# MCU025B_XDS110_USB_Power.net
KiCad netlist of a schematic drawn in Altium Designer
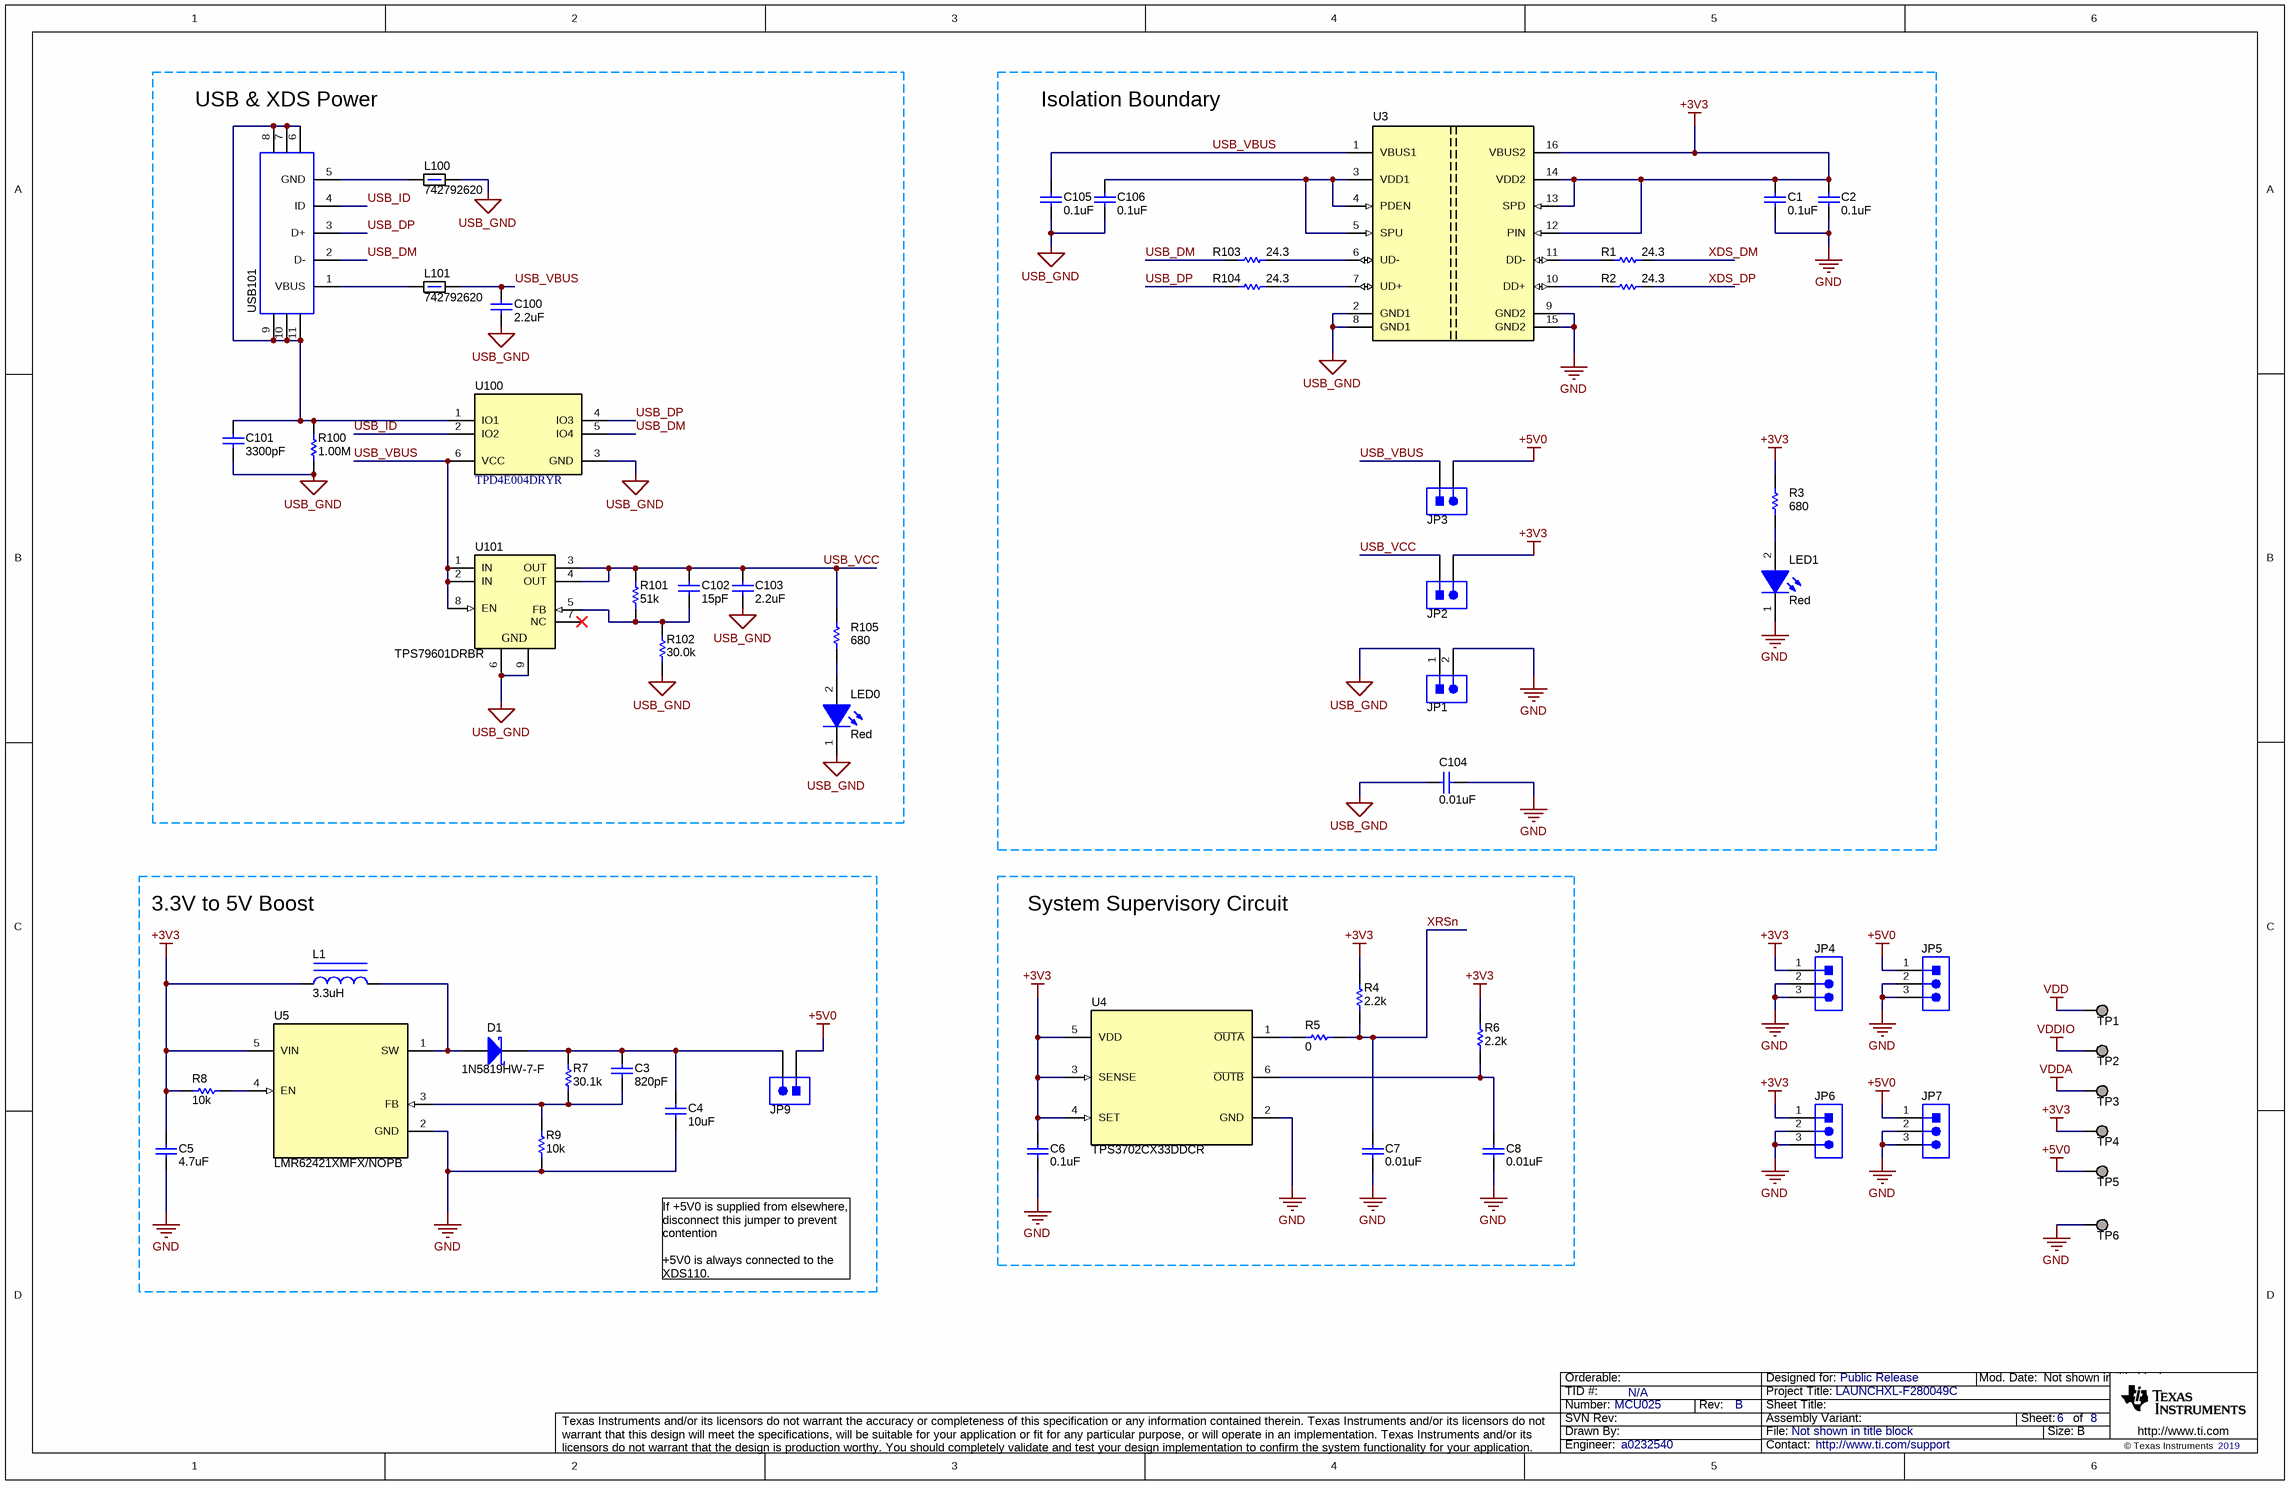
[diagram p0: MCU025B_XDS110_USB_Power.SchDoc]

(export (version "E")
  (design (tool "Eeschema 10.0.6"))
  (components
    (comp (ref "C1")
      (value "GRM155R71A104KA01D")
      (footprint "0402")
      (description "CAP, CERM, 0.1 uF, 10 V, +/- 10%, X7R, 0402")
      (fields
        (field (name "VALUEDISPLAYED") "0.1uF")
        (field (name "MANUFACTURER") "MuRata")
        (field (name "PUBLISHER") "Texas Instruments")
      )
      (libsource (lib "Altium Vault - TI") (part "Capacitor"))
    )
    (comp (ref "C2")
      (value "GRM155R71A104KA01D")
      (footprint "0402")
      (description "CAP, CERM, 0.1 uF, 10 V, +/- 10%, X7R, 0402")
      (fields
        (field (name "VALUEDISPLAYED") "0.1uF")
        (field (name "MANUFACTURER") "MuRata")
        (field (name "PUBLISHER") "Texas Instruments")
      )
      (libsource (lib "Altium Vault - TI") (part "Capacitor"))
    )
    (comp (ref "C3")
      (value "GRM1555C1H821JA01D")
      (footprint "0402")
      (description "CAP, CERM, 820 pF, 50 V, +/- 5%, C0G/NP0, 0402")
      (fields
        (field (name "VALUEDISPLAYED") "820pF")
        (field (name "MANUFACTURER") "MuRata")
        (field (name "PUBLISHER") "Texas Instruments")
      )
      (libsource (lib "Altium Vault - TI") (part "Capacitor"))
    )
    (comp (ref "C4")
      (value "GRM32DR71E106KA12L")
      (footprint "1210_220")
      (description "CAP, CERM, 10 uF, 25 V, +/- 10%, X7R, 1210")
      (fields
        (field (name "VALUEDISPLAYED") "10uF")
        (field (name "MANUFACTURER") "MuRata")
        (field (name "PUBLISHER") "Texas Instruments")
      )
      (libsource (lib "Altium Vault - TI") (part "Capacitor"))
    )
    (comp (ref "C5")
      (value "GRM155R60J475ME47D")
      (footprint "0402")
      (description "CAP, CERM, 4.7 uF, 6.3 V, +/- 20%, X5R, 0402")
      (fields
        (field (name "VALUEDISPLAYED") "4.7uF")
        (field (name "MANUFACTURER") "MuRata")
        (field (name "PUBLISHER") "Texas Instruments")
      )
      (libsource (lib "Altium Vault - TI") (part "Capacitor"))
    )
    (comp (ref "C6")
      (value "GRM155R71A104KA01D")
      (footprint "0402")
      (description "CAP, CERM, 0.1 uF, 10 V, +/- 10%, X7R, 0402")
      (fields
        (field (name "VALUEDISPLAYED") "0.1uF")
        (field (name "MANUFACTURER") "MuRata")
        (field (name "PUBLISHER") "Texas Instruments")
      )
      (libsource (lib "Altium Vault - TI") (part "Capacitor"))
    )
    (comp (ref "C7")
      (value "GRM155R71E103KA01D")
      (footprint "0402")
      (description "CAP, CERM, 0.01 uF, 25 V, +/- 10%, X7R, 0402")
      (fields
        (field (name "VALUEDISPLAYED") "0.01uF")
        (field (name "MANUFACTURER") "MuRata")
        (field (name "PUBLISHER") "Texas Instruments")
      )
      (libsource (lib "Altium Vault - TI") (part "Capacitor"))
    )
    (comp (ref "C8")
      (value "GRM155R71E103KA01D")
      (footprint "0402")
      (description "CAP, CERM, 0.01 uF, 25 V, +/- 10%, X7R, 0402")
      (fields
        (field (name "VALUEDISPLAYED") "0.01uF")
        (field (name "MANUFACTURER") "MuRata")
        (field (name "PUBLISHER") "Texas Instruments")
      )
      (libsource (lib "Altium Vault - TI") (part "Capacitor"))
    )
    (comp (ref "C100")
      (value "GRM155R60J225KE95D")
      (footprint "0402")
      (description "CAP, CERM, 2.2 uF, 6.3 V, +/- 10%, X5R, 0402")
      (fields
        (field (name "VALUEDISPLAYED") "2.2uF")
        (field (name "MANUFACTURER") "MuRata")
        (field (name "PUBLISHER") "Texas Instruments")
      )
      (libsource (lib "Altium Vault - TI") (part "Capacitor"))
    )
    (comp (ref "C101")
      (value "GRM155R71H332KA01D")
      (footprint "0402")
      (description "CAP, CERM, 3300 pF, 50 V, +/- 10%, X7R, 0402")
      (fields
        (field (name "VALUEDISPLAYED") "3300pF")
        (field (name "MANUFACTURER") "MuRata")
        (field (name "PUBLISHER") "Texas Instruments")
      )
      (libsource (lib "Altium Vault - TI") (part "Capacitor"))
    )
    (comp (ref "C102")
      (value "GRM1555C1H150JA01D")
      (footprint "0402")
      (description "CAP, CERM, 15 pF, 50 V, +/- 5%, C0G/NP0, 0402")
      (fields
        (field (name "VALUEDISPLAYED") "15pF")
        (field (name "MANUFACTURER") "MuRata")
        (field (name "PUBLISHER") "Texas Instruments")
      )
      (libsource (lib "Altium Vault - TI") (part "Capacitor"))
    )
    (comp (ref "C103")
      (value "GRM155R60J225KE95D")
      (footprint "0402")
      (description "CAP, CERM, 2.2 uF, 6.3 V, +/- 10%, X5R, 0402")
      (fields
        (field (name "VALUEDISPLAYED") "2.2uF")
        (field (name "MANUFACTURER") "MuRata")
        (field (name "PUBLISHER") "Texas Instruments")
      )
      (libsource (lib "Altium Vault - TI") (part "Capacitor"))
    )
    (comp (ref "C104")
      (value "1812SC103KAT1A")
      (footprint "1812")
      (description "CAP, CERM, 0.01 uF, 1500 V, +/- 10%, X7R, 1812")
      (fields
        (field (name "VALUEDISPLAYED") "0.01uF")
        (field (name "MANUFACTURER") "AVX")
        (field (name "PUBLISHER") "Texas Instruments")
      )
      (libsource (lib "Altium Vault - TI") (part "Capacitor"))
    )
    (comp (ref "C105")
      (value "GRM155R71A104KA01D")
      (footprint "0402")
      (description "CAP, CERM, 0.1 uF, 10 V, +/- 10%, X7R, 0402")
      (fields
        (field (name "VALUEDISPLAYED") "0.1uF")
        (field (name "MANUFACTURER") "MuRata")
        (field (name "PUBLISHER") "Texas Instruments")
      )
      (libsource (lib "Altium Vault - TI") (part "Capacitor"))
    )
    (comp (ref "C106")
      (value "GRM155R71A104KA01D")
      (footprint "0402")
      (description "CAP, CERM, 0.1 uF, 10 V, +/- 10%, X7R, 0402")
      (fields
        (field (name "VALUEDISPLAYED") "0.1uF")
        (field (name "MANUFACTURER") "MuRata")
        (field (name "PUBLISHER") "Texas Instruments")
      )
      (libsource (lib "Altium Vault - TI") (part "Capacitor"))
    )
    (comp (ref "D1")
      (value "1N5819HW-7-F")
      (footprint "SOD-123")
      (description "Diode, Schottky, 40 V, 1 A, SOD-123")
      (fields (field (name "MANUFACTURER") "Diodes Inc.") (field (name "PUBLISHER") "Texas Instruments"))
      (libsource (lib "Altium Vault - TI") (part "DIODE_SCHOTTKY"))
    )
    (comp (ref "JP1")
      (value "61300211121")
      (footprint "WURTH_61300211121")
      (description "Header, 2.54 mm, 2x1, Gold, TH")
      (fields (field (name "MANUFACTURER") "Wurth Elektronik") (field (name "PUBLISHER") "Texas Instruments"))
      (libsource (lib "Altium Vault - TI") (part "Header_2x1"))
    )
    (comp (ref "JP2")
      (value "61300211121")
      (footprint "WURTH_61300211121")
      (description "Header, 2.54 mm, 2x1, Gold, TH")
      (fields (field (name "MANUFACTURER") "Wurth Elektronik") (field (name "PUBLISHER") "Texas Instruments"))
      (libsource (lib "Altium Vault - TI") (part "CMP-0054794-1"))
    )
    (comp (ref "JP3")
      (value "61300211121")
      (footprint "WURTH_61300211121")
      (description "Header, 2.54 mm, 2x1, Gold, TH")
      (fields (field (name "MANUFACTURER") "Wurth Elektronik") (field (name "PUBLISHER") "Texas Instruments"))
      (libsource (lib "Altium Vault - TI") (part "CMP-0054794-1"))
    )
    (comp (ref "JP4")
      (value "61300311121")
      (footprint "WURTH_61300311121")
      (description "Header, 2.54 mm, 3x1, Gold, TH")
      (fields (field (name "MANUFACTURER") "Wurth Elektronik") (field (name "PUBLISHER") "Texas Instruments"))
      (libsource (lib "Altium Vault - TI") (part "Header_3x1"))
    )
    (comp (ref "JP5")
      (value "61300311121")
      (footprint "WURTH_61300311121")
      (description "Header, 2.54 mm, 3x1, Gold, TH")
      (fields (field (name "MANUFACTURER") "Wurth Elektronik") (field (name "PUBLISHER") "Texas Instruments"))
      (libsource (lib "Altium Vault - TI") (part "Header_3x1"))
    )
    (comp (ref "JP6")
      (value "61300311121")
      (footprint "WURTH_61300311121")
      (description "Header, 2.54 mm, 3x1, Gold, TH")
      (fields (field (name "MANUFACTURER") "Wurth Elektronik") (field (name "PUBLISHER") "Texas Instruments"))
      (libsource (lib "Altium Vault - TI") (part "Header_3x1"))
    )
    (comp (ref "JP7")
      (value "61300311121")
      (footprint "WURTH_61300311121")
      (description "Header, 2.54 mm, 3x1, Gold, TH")
      (fields (field (name "MANUFACTURER") "Wurth Elektronik") (field (name "PUBLISHER") "Texas Instruments"))
      (libsource (lib "Altium Vault - TI") (part "Header_3x1"))
    )
    (comp (ref "JP9")
      (value "61300211121")
      (footprint "WURTH_61300211121")
      (description "Header, 2.54 mm, 2x1, Gold, TH")
      (fields (field (name "MANUFACTURER") "Wurth Elektronik") (field (name "PUBLISHER") "Texas Instruments"))
      (libsource (lib "") (part "CMP-0054794-1_1"))
    )
    (comp (ref "L1")
      (value "744025003")
      (footprint "WE-TPC_2828")
      (description "Inductor, Shielded Drum Core, Ferrite, 3.3 uH, 1.5 A, 0.085 ohm, SMD")
      (fields
        (field (name "VALUEDISPLAYED") "3.3uH")
        (field (name "MANUFACTURER") "Wurth Elektronik")
        (field (name "PUBLISHER") "Texas Instruments")
      )
      (libsource (lib "Altium Vault - TI") (part "Inductor_Iron"))
    )
    (comp (ref "L100")
      (value "742792620")
      (footprint "0603")
      (description "Ferrite Bead, 100 ohm @ 100 MHz, 0.5 A, 0603")
      (fields (field (name "MANUFACTURER") "Wurth Elektronik") (field (name "PUBLISHER") "Texas Instruments"))
      (libsource (lib "Altium Vault - TI") (part "Ferrite_Bead"))
    )
    (comp (ref "L101")
      (value "742792620")
      (footprint "0603")
      (description "Ferrite Bead, 100 ohm @ 100 MHz, 0.5 A, 0603")
      (fields (field (name "MANUFACTURER") "Wurth Elektronik") (field (name "PUBLISHER") "Texas Instruments"))
      (libsource (lib "Altium Vault - TI") (part "Ferrite_Bead"))
    )
    (comp (ref "LED0")
      (value "Red")
      (footprint "WL-SMCW_RED_0805")
      (description "LED, Red, SMD")
      (fields
        (field (name "MANUFACTURER") "Wurth Elektronik")
        (field (name "PARTNUMBER") "150080SS75000")
        (field (name "PUBLISHER") "Texas Instruments")
      )
      (libsource (lib "Altium Vault - TI") (part "LED_A2_K1"))
    )
    (comp (ref "LED1")
      (value "Red")
      (footprint "WL-SMCW_RED_0805")
      (description "LED, Red, SMD")
      (fields
        (field (name "MANUFACTURER") "Wurth Elektronik")
        (field (name "PARTNUMBER") "150080SS75000")
        (field (name "PUBLISHER") "Texas Instruments")
      )
      (libsource (lib "Altium Vault - TI") (part "LED_A2_K1"))
    )
    (comp (ref "R1")
      (value "CRCW040224R3FKED")
      (footprint "0402")
      (description "RES, 24.3, 1%, 0.063 W, AEC-Q200 Grade 0, 0402")
      (fields (field (name "VALUEDISPLAYED") "24.3") (field (name "MANUFACTURER") "Vishay-Dale"))
      (libsource (lib "Altium Vault - TI") (part "Resistor"))
    )
    (comp (ref "R2")
      (value "CRCW040224R3FKED")
      (footprint "0402")
      (description "RES, 24.3, 1%, 0.063 W, AEC-Q200 Grade 0, 0402")
      (fields (field (name "VALUEDISPLAYED") "24.3") (field (name "MANUFACTURER") "Vishay-Dale"))
      (libsource (lib "Altium Vault - TI") (part "Resistor"))
    )
    (comp (ref "R3")
      (value "CRCW0402680RJNED")
      (footprint "0402")
      (description "RES, 680, 5%, 0.063 W, AEC-Q200 Grade 0, 0402")
      (fields (field (name "MANUFACTURER") "Vishay-Dale") (field (name "VALUEDISPLAYED") "680"))
      (libsource (lib "Altium Vault - TI") (part "CMP-0026962-3"))
    )
    (comp (ref "R4")
      (value "CRCW04022K20JNED")
      (footprint "0402")
      (description "RES, 2.2 k, 5%, 0.063 W, AEC-Q200 Grade 0, 0402")
      (fields (field (name "VALUEDISPLAYED") "2.2k") (field (name "MANUFACTURER") "Vishay-Dale"))
      (libsource (lib "Altium Vault - TI") (part "Resistor"))
    )
    (comp (ref "R5")
      (value "CRCW04020000Z0ED")
      (footprint "0402")
      (description "RES, 0, 5%, 0.063 W, AEC-Q200 Grade 0, 0402")
      (fields (field (name "VALUEDISPLAYED") "0") (field (name "MANUFACTURER") "Vishay-Dale"))
      (libsource (lib "Altium Vault - TI") (part "Resistor"))
    )
    (comp (ref "R6")
      (value "CRCW06032K20JNEA")
      (footprint "0603")
      (description "RES, 2.2 k, 5%, 0.1 W, AEC-Q200 Grade 0, 0603")
      (fields (field (name "VALUEDISPLAYED") "2.2k") (field (name "MANUFACTURER") "Vishay-Dale"))
      (libsource (lib "Altium Vault - TI") (part "Resistor"))
    )
    (comp (ref "R7")
      (value "RC0402FR-0730K1L")
      (footprint "0402")
      (description "RES, 30.1 k, 1%, 0.063 W, 0402")
      (fields
        (field (name "VALUEDISPLAYED") "30.1k")
        (field (name "MANUFACTURER") "Yageo America")
        (field (name "PUBLISHER") "Texas Instruments")
      )
      (libsource (lib "Altium Vault - TI") (part "Resistor"))
    )
    (comp (ref "R8")
      (value "CRCW040210K0JNED")
      (footprint "0402")
      (description "RES, 10 k, 5%, 0.063 W, AEC-Q200 Grade 0, 0402")
      (fields (field (name "VALUEDISPLAYED") "10k") (field (name "MANUFACTURER") "Vishay-Dale"))
      (libsource (lib "Altium Vault - TI") (part "Resistor"))
    )
    (comp (ref "R9")
      (value "CRCW040210K0JNED")
      (footprint "0402")
      (description "RES, 10 k, 5%, 0.063 W, AEC-Q200 Grade 0, 0402")
      (fields (field (name "VALUEDISPLAYED") "10k") (field (name "MANUFACTURER") "Vishay-Dale"))
      (libsource (lib "Altium Vault - TI") (part "Resistor"))
    )
    (comp (ref "R100")
      (value "CRCW04021M00FKED")
      (footprint "0402")
      (description "RES, 1.00 M, 1%, 0.063 W, AEC-Q200 Grade 0, 0402")
      (fields (field (name "VALUEDISPLAYED") "1.00M") (field (name "MANUFACTURER") "Vishay-Dale"))
      (libsource (lib "Altium Vault - TI") (part "Resistor"))
    )
    (comp (ref "R101")
      (value "CRCW040251K0FKED")
      (footprint "0402")
      (description "RES Thick Film SMD 51kΩ 1% 1/16W 0402 100ppm/K")
      (fields (field (name "MANUFACTURER") "Vishay") (field (name "VALUEDISPLAYED") "51k"))
      (libsource (lib "Altium Vault - TI") (part "Resistor"))
    )
    (comp (ref "R102")
      (value "CRCW040230K0FKED")
      (footprint "0402")
      (description "RES, 30.0 k, 1%, 0.063 W, AEC-Q200 Grade 0, 0402")
      (fields (field (name "MANUFACTURER") "Vishay-Dale") (field (name "VALUEDISPLAYED") "30.0k"))
      (libsource (lib "Altium Vault - TI") (part "Resistor"))
    )
    (comp (ref "R103")
      (value "CRCW040224R3FKED")
      (footprint "0402")
      (description "RES, 24.3, 1%, 0.063 W, AEC-Q200 Grade 0, 0402")
      (fields (field (name "VALUEDISPLAYED") "24.3") (field (name "MANUFACTURER") "Vishay-Dale"))
      (libsource (lib "Altium Vault - TI") (part "Resistor"))
    )
    (comp (ref "R104")
      (value "CRCW040224R3FKED")
      (footprint "0402")
      (description "RES, 24.3, 1%, 0.063 W, AEC-Q200 Grade 0, 0402")
      (fields (field (name "VALUEDISPLAYED") "24.3") (field (name "MANUFACTURER") "Vishay-Dale"))
      (libsource (lib "Altium Vault - TI") (part "Resistor"))
    )
    (comp (ref "R105")
      (value "CRCW0402680RJNED")
      (footprint "0402")
      (description "RES, 680, 5%, 0.063 W, AEC-Q200 Grade 0, 0402")
      (fields (field (name "MANUFACTURER") "Vishay-Dale") (field (name "VALUEDISPLAYED") "680"))
      (libsource (lib "Altium Vault - TI") (part "CMP-0026962-3"))
    )
    (comp (ref "TP1")
      (value "TESTPOINT")
      (footprint "TESTPOINT")
      (description "TEST POINT.  No entry in BOM.")
      (libsource (lib "Altium Vault - TI") (part "TESTPOINT"))
    )
    (comp (ref "TP2")
      (value "TESTPOINT")
      (footprint "TESTPOINT")
      (description "TEST POINT.  No entry in BOM.")
      (libsource (lib "Altium Vault - TI") (part "TESTPOINT"))
    )
    (comp (ref "TP3")
      (value "TESTPOINT")
      (footprint "TESTPOINT")
      (description "TEST POINT.  No entry in BOM.")
      (libsource (lib "Altium Vault - TI") (part "TESTPOINT"))
    )
    (comp (ref "TP4")
      (value "TESTPOINT")
      (footprint "TESTPOINT")
      (description "TEST POINT.  No entry in BOM.")
      (libsource (lib "Altium Vault - TI") (part "TESTPOINT"))
    )
    (comp (ref "TP5")
      (value "TESTPOINT")
      (footprint "TESTPOINT")
      (description "TEST POINT.  No entry in BOM.")
      (libsource (lib "Altium Vault - TI") (part "TESTPOINT"))
    )
    (comp (ref "TP6")
      (value "TESTPOINT")
      (footprint "TESTPOINT")
      (description "TEST POINT.  No entry in BOM.")
      (libsource (lib "Altium Vault - TI") (part "TESTPOINT"))
    )
    (comp (ref "U3")
      (value "ADuM3160BRWZ")
      (footprint "SOIC-16")
      (description "Full/Low Speed 2.5 kV USB Digital Isolator, SOIC-16")
      (fields (field (name "MANUFACTURER") "Analog Devices") (field (name "PUBLISHER") "Texas Instruments"))
      (libsource (lib "Altium Vault - TI") (part "ADuM3160"))
    )
    (comp (ref "U4")
      (value "TPS3702CX33DDCR")
      (footprint "DDC0006A_N")
      (description "High-Accuracy, Fixed-Threshold OV/UV Monitor, DDC0006A (SOT-23-T-6)")
      (fields
        (field (name "ALTERNATE PARTNUMBER") "TPS3702CX33DDCT")
        (field (name "MANUFACTURER") "Texas Instruments")
        (field (name "PUBLISHER") "Texas Instruments")
      )
      (libsource (lib "Altium Vault - TI") (part "TPS3702"))
    )
    (comp (ref "U5")
      (value "LMR62421XMFX/NOPB")
      (footprint "DBV0005A_N")
      (description "SIMPLE SWITCHER 2.7V to 5.5V, 2.1A Step-Up Regulator in SOT-23, DBV0005A (SOT-23-5)")
      (fields
        (field (name "ALTERNATE PARTNUMBER") "LMR62421XMFE/NOPB")
        (field (name "MANUFACTURER") "Texas Instruments")
        (field (name "PUBLISHER") "Texas Instruments")
      )
      (libsource (lib "Altium Vault - TI") (part "LMR62421DBV"))
    )
    (comp (ref "U100")
      (value "TPD4E004DRYR")
      (footprint "DRY0006A")
      (fields (field (name "MANUFACTURER") "Texas Instruments"))
      (libsource (lib "Altium Vault - TI") (part "TI-TPD4E004-SON_DRY-6"))
    )
    (comp (ref "U101")
      (value "TPS79601DRBR")
      (footprint "DRB0008B")
      (fields (field (name "MANUFACTURER") "Texas Instruments"))
      (libsource (lib "Altium Vault - TI") (part "CMP-0036402-3"))
    )
    (comp (ref "USB101")
      (value "1051640001")
      (footprint "Molex_1051640001")
      (description "Receptacle, USB 2.0, Micro B, 5 Position, R/A, SMT")
      (fields (field (name "MANUFACTURER") "Molex") (field (name "PUBLISHER") "Texas Instruments"))
      (libsource (lib "Altium Vault - TI") (part "CONN_USB_MicroMini_6Shld"))
    )
  )
  (nets
    (net (code "1") (name "+3V3") (class "Default")
      (node (ref "C1") (pin "2") (pinfunction "2_2") (pintype "passive"))
      (node (ref "C2") (pin "2") (pinfunction "2_2") (pintype "passive"))
      (node (ref "C5") (pin "1") (pinfunction "1_1") (pintype "passive"))
      (node (ref "C6") (pin "2") (pinfunction "2_2") (pintype "passive"))
      (node (ref "JP2") (pin "2") (pinfunction "2_2") (pintype "passive"))
      (node (ref "JP4") (pin "1") (pinfunction "1_1") (pintype "passive"))
      (node (ref "JP6") (pin "1") (pinfunction "1_1") (pintype "passive"))
      (node (ref "L1") (pin "1") (pinfunction "1_1") (pintype "passive"))
      (node (ref "R3") (pin "2") (pinfunction "2_2") (pintype "passive"))
      (node (ref "R4") (pin "2") (pinfunction "2_2") (pintype "passive"))
      (node (ref "R6") (pin "2") (pinfunction "2_2") (pintype "passive"))
      (node (ref "R8") (pin "2") (pinfunction "2_2") (pintype "passive"))
      (node (ref "TP4") (pin "1") (pintype "passive"))
      (node (ref "U3") (pin "12") (pinfunction "PIN_12") (pintype "input"))
      (node (ref "U3") (pin "13") (pinfunction "SPD_13") (pintype "input"))
      (node (ref "U3") (pin "14") (pinfunction "VDD2_14") (pintype "power_in"))
      (node (ref "U3") (pin "16") (pinfunction "VBUS2_16") (pintype "power_in"))
      (node (ref "U4") (pin "3") (pinfunction "SENSE_3") (pintype "input"))
      (node (ref "U4") (pin "4") (pinfunction "SET_4") (pintype "input"))
      (node (ref "U4") (pin "5") (pinfunction "VDD_5") (pintype "power_in"))
      (node (ref "U5") (pin "5") (pinfunction "VIN_5") (pintype "power_in"))
    )
    (net (code "2") (name "+5V0") (class "Default")
      (node (ref "JP3") (pin "2") (pinfunction "2_2") (pintype "passive"))
      (node (ref "JP5") (pin "1") (pinfunction "1_1") (pintype "passive"))
      (node (ref "JP7") (pin "1") (pinfunction "1_1") (pintype "passive"))
      (node (ref "JP9") (pin "1") (pinfunction "1_1") (pintype "passive"))
      (node (ref "TP5") (pin "1") (pintype "passive"))
    )
    (net (code "3") (name "/USB_DM") (class "Default")
      (node (ref "R103") (pin "1") (pinfunction "1_1") (pintype "passive"))
      (node (ref "U100") (pin "5") (pinfunction "IO4_5") (pintype "passive"))
      (node (ref "USB101") (pin "2") (pinfunction "D-_2") (pintype "passive"))
    )
    (net (code "4") (name "/USB_DP") (class "Default")
      (node (ref "R104") (pin "1") (pinfunction "1_1") (pintype "passive"))
      (node (ref "U100") (pin "4") (pinfunction "IO3_4") (pintype "passive"))
      (node (ref "USB101") (pin "3") (pinfunction "D+_3") (pintype "passive"))
    )
    (net (code "5") (name "/USB_ID") (class "Default")
      (node (ref "U100") (pin "2") (pinfunction "IO2_2") (pintype "passive"))
      (node (ref "USB101") (pin "4") (pinfunction "ID_4") (pintype "passive"))
    )
    (net (code "6") (name "/USB_VBUS") (class "Default")
      (node (ref "C100") (pin "1") (pinfunction "1_1") (pintype "passive"))
      (node (ref "C105") (pin "2") (pinfunction "2_2") (pintype "passive"))
      (node (ref "JP3") (pin "1") (pinfunction "1_1") (pintype "passive"))
      (node (ref "L101") (pin "2") (pinfunction "2_2") (pintype "passive"))
      (node (ref "U100") (pin "6") (pinfunction "VCC_6") (pintype "power_in"))
      (node (ref "U101") (pin "1") (pinfunction "IN_1") (pintype "power_in"))
      (node (ref "U101") (pin "2") (pinfunction "IN_2") (pintype "power_in"))
      (node (ref "U101") (pin "8") (pinfunction "EN_8") (pintype "input"))
      (node (ref "U3") (pin "1") (pinfunction "VBUS1_1") (pintype "power_in"))
    )
    (net (code "7") (name "/USB_VCC") (class "Default")
      (node (ref "C102") (pin "1") (pinfunction "1_1") (pintype "passive"))
      (node (ref "C103") (pin "1") (pinfunction "1_1") (pintype "passive"))
      (node (ref "JP2") (pin "1") (pinfunction "1_1") (pintype "passive"))
      (node (ref "R101") (pin "2") (pinfunction "2_2") (pintype "passive"))
      (node (ref "R105") (pin "2") (pinfunction "2_2") (pintype "passive"))
      (node (ref "U101") (pin "3") (pinfunction "OUT_3") (pintype "power_in"))
      (node (ref "U101") (pin "4") (pinfunction "OUT_4") (pintype "power_in"))
    )
    (net (code "8") (name "/XDS_DM") (class "Default")
      (node (ref "R1") (pin "2") (pinfunction "2_2") (pintype "passive"))
    )
    (net (code "9") (name "/XDS_DP") (class "Default")
      (node (ref "R2") (pin "2") (pinfunction "2_2") (pintype "passive"))
    )
    (net (code "10") (name "/XRSn") (class "Default")
      (node (ref "C7") (pin "1") (pinfunction "1_1") (pintype "passive"))
      (node (ref "R4") (pin "1") (pinfunction "1_1") (pintype "passive"))
      (node (ref "R5") (pin "2") (pinfunction "2_2") (pintype "passive"))
    )
    (net (code "11") (name "GND") (class "Default")
      (node (ref "C1") (pin "1") (pinfunction "1_1") (pintype "passive"))
      (node (ref "C104") (pin "1") (pinfunction "1_1") (pintype "passive"))
      (node (ref "C2") (pin "1") (pinfunction "1_1") (pintype "passive"))
      (node (ref "C4") (pin "2") (pinfunction "2_2") (pintype "passive"))
      (node (ref "C5") (pin "2") (pinfunction "2_2") (pintype "passive"))
      (node (ref "C6") (pin "1") (pinfunction "1_1") (pintype "passive"))
      (node (ref "C7") (pin "2") (pinfunction "2_2") (pintype "passive"))
      (node (ref "C8") (pin "2") (pinfunction "2_2") (pintype "passive"))
      (node (ref "JP1") (pin "2") (pinfunction "2_2") (pintype "passive"))
      (node (ref "JP4") (pin "2") (pinfunction "2_2") (pintype "passive"))
      (node (ref "JP4") (pin "3") (pinfunction "3_3") (pintype "passive"))
      (node (ref "JP5") (pin "2") (pinfunction "2_2") (pintype "passive"))
      (node (ref "JP5") (pin "3") (pinfunction "3_3") (pintype "passive"))
      (node (ref "JP6") (pin "2") (pinfunction "2_2") (pintype "passive"))
      (node (ref "JP6") (pin "3") (pinfunction "3_3") (pintype "passive"))
      (node (ref "JP7") (pin "2") (pinfunction "2_2") (pintype "passive"))
      (node (ref "JP7") (pin "3") (pinfunction "3_3") (pintype "passive"))
      (node (ref "LED1") (pin "1") (pinfunction "K_1") (pintype "passive"))
      (node (ref "R9") (pin "1") (pinfunction "1_1") (pintype "passive"))
      (node (ref "TP6") (pin "1") (pintype "passive"))
      (node (ref "U3") (pin "15") (pinfunction "GND2_15") (pintype "power_in"))
      (node (ref "U3") (pin "9") (pinfunction "GND2_9") (pintype "power_in"))
      (node (ref "U4") (pin "2") (pinfunction "GND_2") (pintype "power_in"))
      (node (ref "U5") (pin "2") (pinfunction "GND_2") (pintype "power_in"))
    )
    (net (code "12") (name "Net-(D1-A)") (class "Default")
      (node (ref "D1") (pin "2") (pinfunction "A_2") (pintype "passive"))
      (node (ref "L1") (pin "2") (pinfunction "2_2") (pintype "passive"))
      (node (ref "U5") (pin "1") (pinfunction "SW_1") (pintype "power_in"))
    )
    (net (code "13") (name "Net-(D1-K)") (class "Default")
      (node (ref "C3") (pin "1") (pinfunction "1_1") (pintype "passive"))
      (node (ref "C4") (pin "1") (pinfunction "1_1") (pintype "passive"))
      (node (ref "D1") (pin "1") (pinfunction "K_1") (pintype "passive"))
      (node (ref "JP9") (pin "2") (pinfunction "2_2") (pintype "passive"))
      (node (ref "R7") (pin "2") (pinfunction "2_2") (pintype "passive"))
    )
    (net (code "14") (name "Net-(LED0-A)") (class "Default")
      (node (ref "LED0") (pin "2") (pinfunction "A_2") (pintype "passive"))
      (node (ref "R105") (pin "1") (pinfunction "1_1") (pintype "passive"))
    )
    (net (code "15") (name "Net-(LED1-A)") (class "Default")
      (node (ref "LED1") (pin "2") (pinfunction "A_2") (pintype "passive"))
      (node (ref "R3") (pin "1") (pinfunction "1_1") (pintype "passive"))
    )
    (net (code "16") (name "Net-(U3-DD+)") (class "Default")
      (node (ref "R2") (pin "1") (pinfunction "1_1") (pintype "passive"))
      (node (ref "U3") (pin "10") (pinfunction "DD+_10") (pintype "bidirectional"))
    )
    (net (code "17") (name "Net-(U3-DD-)") (class "Default")
      (node (ref "R1") (pin "1") (pinfunction "1_1") (pintype "passive"))
      (node (ref "U3") (pin "11") (pinfunction "DD-_11") (pintype "bidirectional"))
    )
    (net (code "18") (name "Net-(U3-PDEN)") (class "Default")
      (node (ref "C106") (pin "2") (pinfunction "2_2") (pintype "passive"))
      (node (ref "U3") (pin "3") (pinfunction "VDD1_3") (pintype "power_in"))
      (node (ref "U3") (pin "4") (pinfunction "PDEN_4") (pintype "input"))
      (node (ref "U3") (pin "5") (pinfunction "SPU_5") (pintype "input"))
    )
    (net (code "19") (name "Net-(U3-UD+)") (class "Default")
      (node (ref "R104") (pin "2") (pinfunction "2_2") (pintype "passive"))
      (node (ref "U3") (pin "7") (pinfunction "UD+_7") (pintype "bidirectional"))
    )
    (net (code "20") (name "Net-(U3-UD-)") (class "Default")
      (node (ref "R103") (pin "2") (pinfunction "2_2") (pintype "passive"))
      (node (ref "U3") (pin "6") (pinfunction "UD-_6") (pintype "bidirectional"))
    )
    (net (code "21") (name "Net-(U4-OUTA)") (class "Default")
      (node (ref "R5") (pin "1") (pinfunction "1_1") (pintype "passive"))
      (node (ref "U4") (pin "1") (pinfunction "OUTA_1") (pintype "open_collector"))
    )
    (net (code "22") (name "Net-(U4-OUTB)") (class "Default")
      (node (ref "C8") (pin "1") (pinfunction "1_1") (pintype "passive"))
      (node (ref "R6") (pin "1") (pinfunction "1_1") (pintype "passive"))
      (node (ref "U4") (pin "6") (pinfunction "OUTB_6") (pintype "open_collector"))
    )
    (net (code "23") (name "Net-(U5-EN)") (class "Default")
      (node (ref "R8") (pin "1") (pinfunction "1_1") (pintype "passive"))
      (node (ref "U5") (pin "4") (pinfunction "EN_4") (pintype "input"))
    )
    (net (code "24") (name "Net-(U5-FB)") (class "Default")
      (node (ref "C3") (pin "2") (pinfunction "2_2") (pintype "passive"))
      (node (ref "R7") (pin "1") (pinfunction "1_1") (pintype "passive"))
      (node (ref "R9") (pin "2") (pinfunction "2_2") (pintype "passive"))
      (node (ref "U5") (pin "3") (pinfunction "FB_3") (pintype "input"))
    )
    (net (code "25") (name "Net-(U100-IO1)") (class "Default")
      (node (ref "C101") (pin "1") (pinfunction "1_1") (pintype "passive"))
      (node (ref "R100") (pin "2") (pinfunction "2_2") (pintype "passive"))
      (node (ref "U100") (pin "1") (pinfunction "IO1_1") (pintype "passive"))
      (node (ref "USB101") (pin "10") (pinfunction "10_10") (pintype "passive"))
      (node (ref "USB101") (pin "11") (pinfunction "11_11") (pintype "passive"))
      (node (ref "USB101") (pin "6") (pinfunction "6_6") (pintype "passive"))
      (node (ref "USB101") (pin "7") (pinfunction "7_7") (pintype "passive"))
      (node (ref "USB101") (pin "8") (pinfunction "8_8") (pintype "passive"))
      (node (ref "USB101") (pin "9") (pinfunction "9_9") (pintype "passive"))
    )
    (net (code "26") (name "Net-(U101-FB)") (class "Default")
      (node (ref "C102") (pin "2") (pinfunction "2_2") (pintype "passive"))
      (node (ref "R101") (pin "1") (pinfunction "1_1") (pintype "passive"))
      (node (ref "R102") (pin "2") (pinfunction "2_2") (pintype "passive"))
      (node (ref "U101") (pin "5") (pinfunction "FB_5") (pintype "input"))
    )
    (net (code "27") (name "Net-(USB101-GND)") (class "Default")
      (node (ref "L100") (pin "1") (pinfunction "1_1") (pintype "passive"))
      (node (ref "USB101") (pin "5") (pinfunction "GND_5") (pintype "passive"))
    )
    (net (code "28") (name "Net-(USB101-VBUS)") (class "Default")
      (node (ref "L101") (pin "1") (pinfunction "1_1") (pintype "passive"))
      (node (ref "USB101") (pin "1") (pinfunction "VBUS_1") (pintype "passive"))
    )
    (net (code "29") (name "USB_GND") (class "Default")
      (node (ref "C100") (pin "2") (pinfunction "2_2") (pintype "passive"))
      (node (ref "C101") (pin "2") (pinfunction "2_2") (pintype "passive"))
      (node (ref "C103") (pin "2") (pinfunction "2_2") (pintype "passive"))
      (node (ref "C104") (pin "2") (pinfunction "2_2") (pintype "passive"))
      (node (ref "C105") (pin "1") (pinfunction "1_1") (pintype "passive"))
      (node (ref "C106") (pin "1") (pinfunction "1_1") (pintype "passive"))
      (node (ref "JP1") (pin "1") (pinfunction "1_1") (pintype "passive"))
      (node (ref "L100") (pin "2") (pinfunction "2_2") (pintype "passive"))
      (node (ref "LED0") (pin "1") (pinfunction "K_1") (pintype "passive"))
      (node (ref "R100") (pin "1") (pinfunction "1_1") (pintype "passive"))
      (node (ref "R102") (pin "1") (pinfunction "1_1") (pintype "passive"))
      (node (ref "U100") (pin "3") (pinfunction "GND_3") (pintype "power_in"))
      (node (ref "U101") (pin "6") (pinfunction "GND_6") (pintype "power_in"))
      (node (ref "U101") (pin "9") (pinfunction "GND_9") (pintype "power_in"))
      (node (ref "U3") (pin "2") (pinfunction "GND1_2") (pintype "power_in"))
      (node (ref "U3") (pin "8") (pinfunction "GND1_8") (pintype "power_in"))
    )
    (net (code "30") (name "VDD") (class "Default") (node (ref "TP1") (pin "1") (pintype "passive")))
    (net (code "31") (name "VDDA") (class "Default") (node (ref "TP3") (pin "1") (pintype "passive")))
    (net (code "32") (name "VDDIO") (class "Default") (node (ref "TP2") (pin "1") (pintype "passive")))
    (net (code "33") (name "unconnected-(U101-NC-Pad7)") (class "Default")
      (node (ref "U101") (pin "7") (pinfunction "NC_7") (pintype "passive+no_connect"))
    )
  )
)
